# main.net
KiCad netlist of a schematic drawn in EAGLE
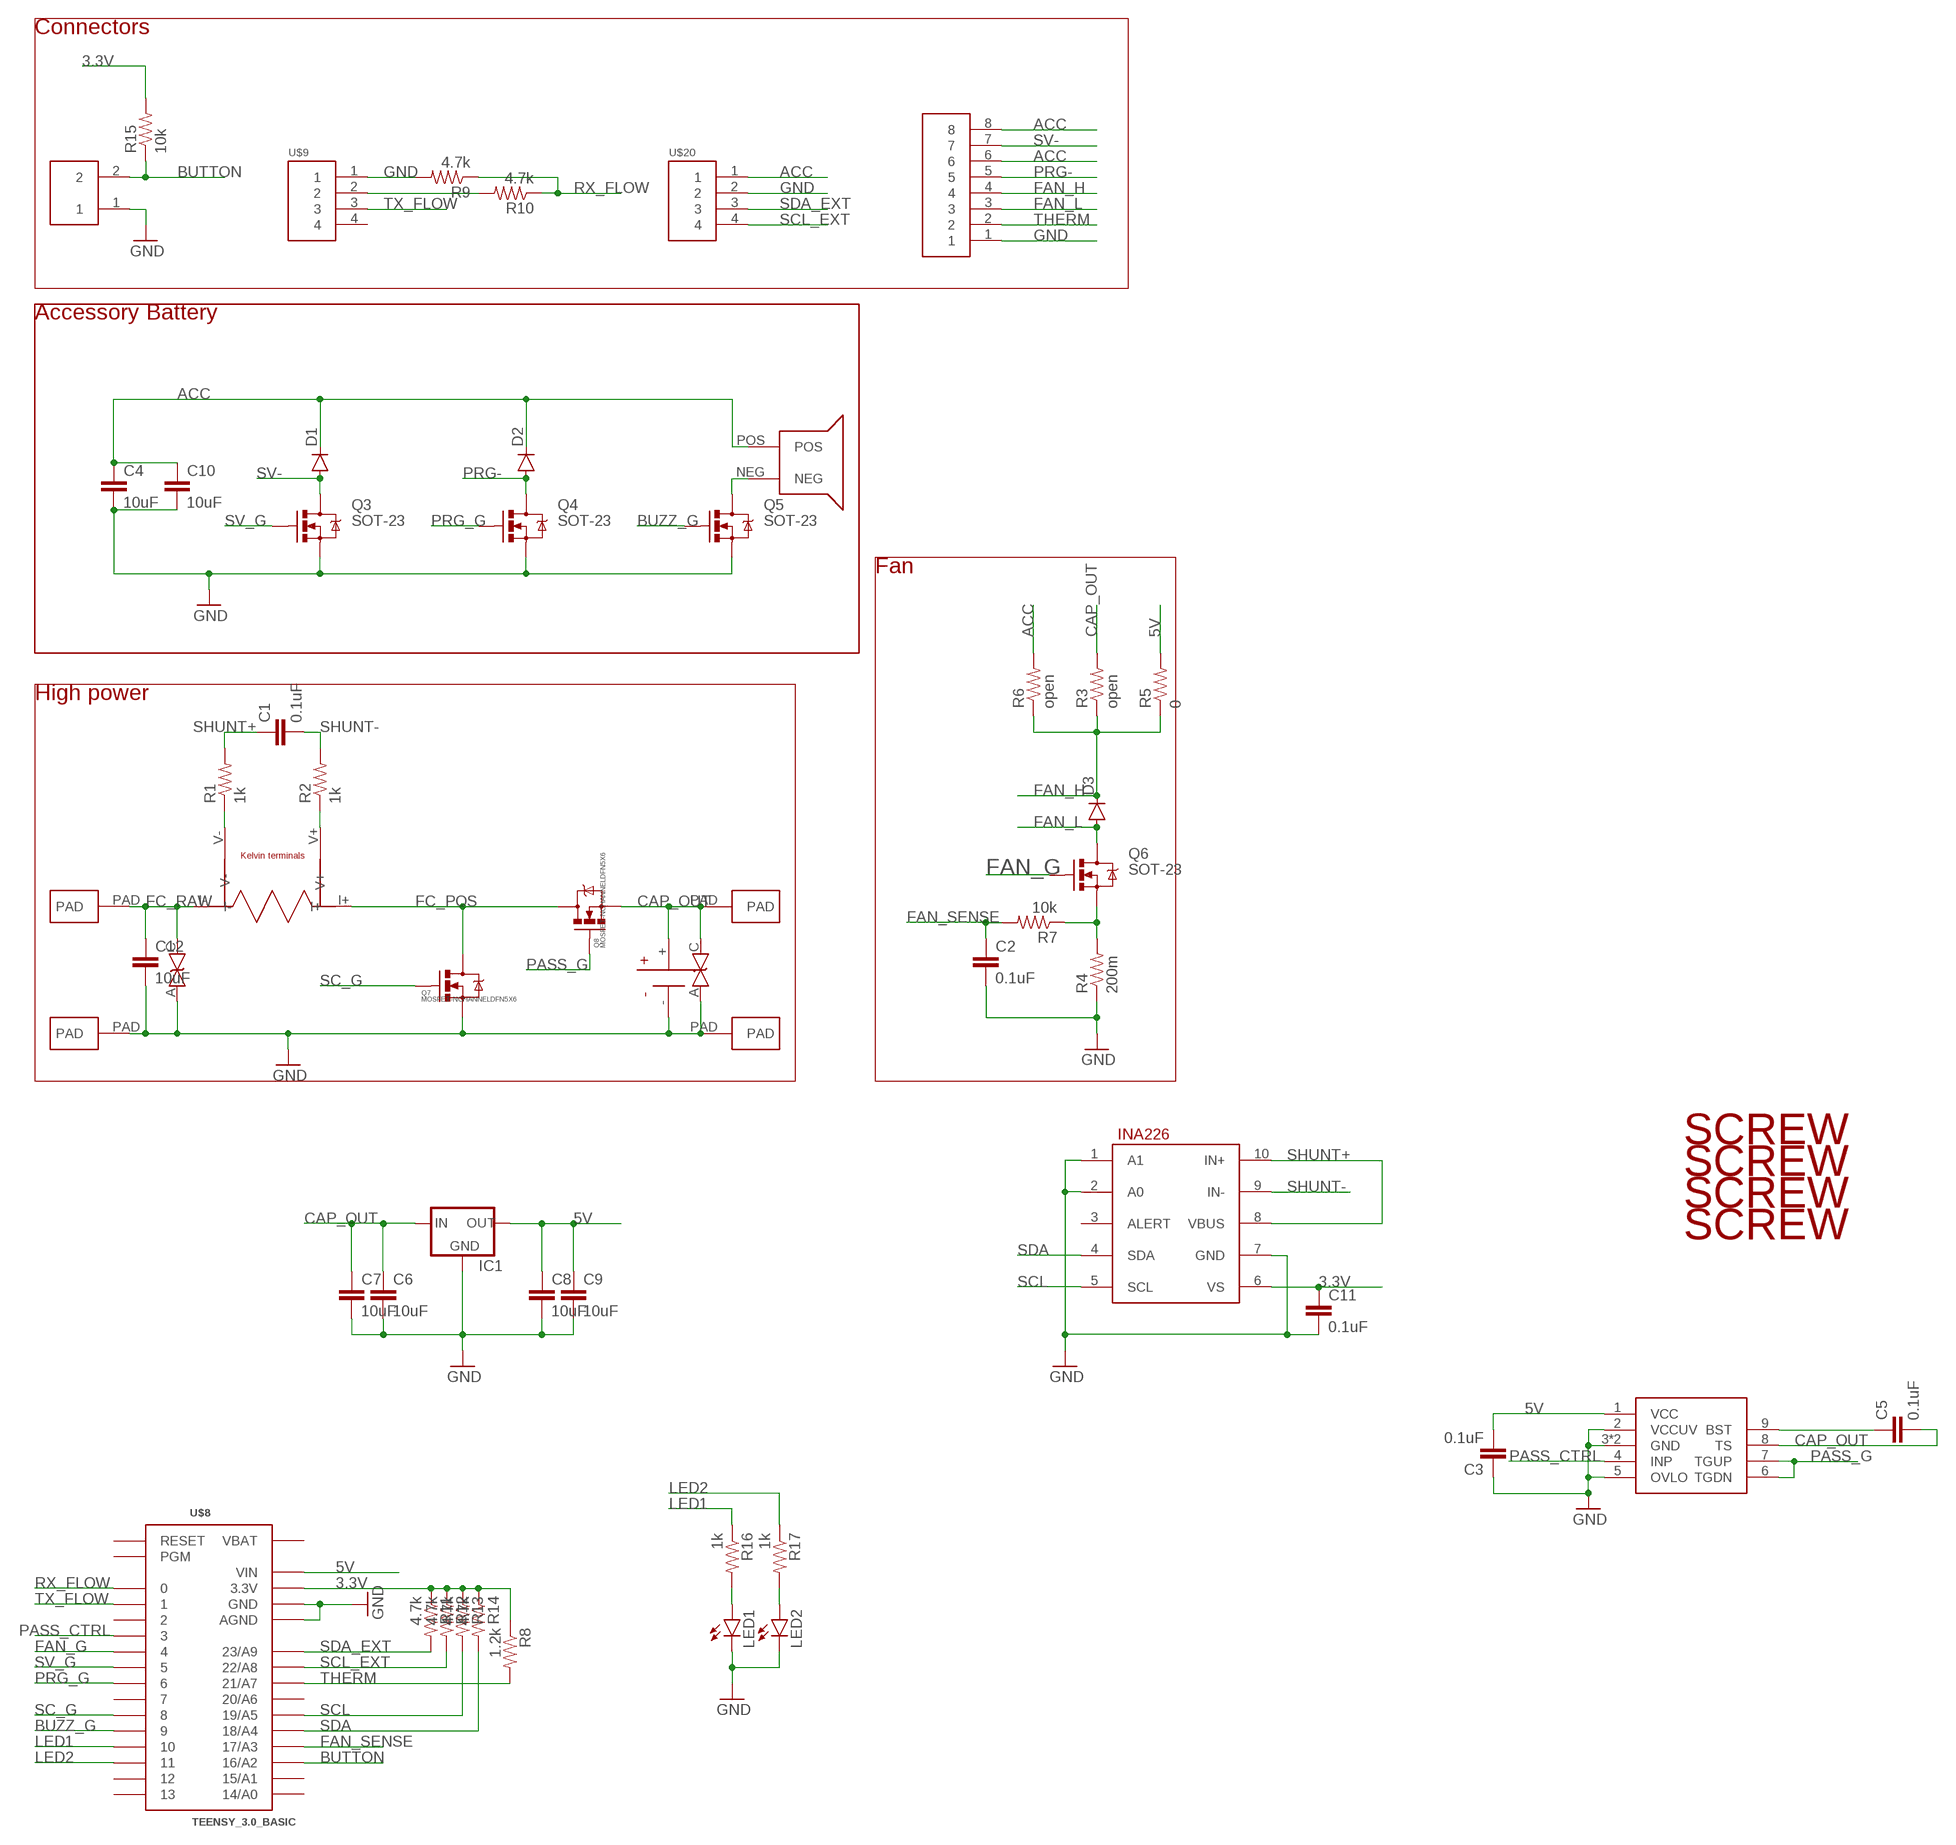
[diagram p0: schematic, sheet 1]

(export (version "E")
  (design (tool "Eeschema 10.0.6"))
  (components
    (comp (ref "C1")
      (value "0.1uF")
      (footprint "eagle-import:0603-CAP")
      (libsource (lib "eagle-import") (part "CAP0603-CAP"))
    )
    (comp (ref "C2")
      (value "0.1uF")
      (footprint "eagle-import:0603-CAP")
      (libsource (lib "eagle-import") (part "CAP0603-CAP"))
    )
    (comp (ref "C3")
      (value "0.1uF")
      (footprint "eagle-import:0603-CAP")
      (libsource (lib "eagle-import") (part "CAP0603-CAP"))
    )
    (comp (ref "C4")
      (value "10uF")
      (footprint "eagle-import:1206")
      (libsource (lib "eagle-import") (part "CAP1206"))
    )
    (comp (ref "C5")
      (value "0.1uF")
      (footprint "eagle-import:0603-CAP")
      (libsource (lib "eagle-import") (part "CAP0603-CAP"))
    )
    (comp (ref "C6")
      (value "10uF")
      (footprint "eagle-import:1206")
      (libsource (lib "eagle-import") (part "CAP1206"))
    )
    (comp (ref "C7")
      (value "10uF")
      (footprint "eagle-import:1206")
      (libsource (lib "eagle-import") (part "CAP1206"))
    )
    (comp (ref "C8")
      (value "10uF")
      (footprint "eagle-import:1206")
      (libsource (lib "eagle-import") (part "CAP1206"))
    )
    (comp (ref "C9")
      (value "10uF")
      (footprint "eagle-import:1206")
      (libsource (lib "eagle-import") (part "CAP1206"))
    )
    (comp (ref "C10")
      (value "10uF")
      (footprint "eagle-import:1206")
      (libsource (lib "eagle-import") (part "CAP1206"))
    )
    (comp (ref "C11")
      (value "0.1uF")
      (footprint "eagle-import:0603-CAP")
      (libsource (lib "eagle-import") (part "CAP0603-CAP"))
    )
    (comp (ref "C12")
      (value "10uF")
      (footprint "eagle-import:1206")
      (libsource (lib "eagle-import") (part "CAP1206"))
    )
    (comp (ref "D1")
      (value "DIODESOD123")
      (footprint "eagle-import:SOD-123")
      (libsource (lib "eagle-import") (part "DIODESOD123"))
    )
    (comp (ref "D2")
      (value "DIODESOD123")
      (footprint "eagle-import:SOD-123")
      (libsource (lib "eagle-import") (part "DIODESOD123"))
    )
    (comp (ref "D3")
      (value "DIODESOD123")
      (footprint "eagle-import:SOD-123")
      (libsource (lib "eagle-import") (part "DIODESOD123"))
    )
    (comp (ref "IC1")
      (value "V_REG_78XXV78W")
      (footprint "eagle-import:V78W")
      (libsource (lib "eagle-import") (part "V_REG_78XXV78W"))
    )
    (comp (ref "LED1")
      (value "LED1206")
      (footprint "eagle-import:LED-1206")
      (libsource (lib "eagle-import") (part "LED1206"))
    )
    (comp (ref "LED2")
      (value "LED1206")
      (footprint "eagle-import:LED-1206")
      (libsource (lib "eagle-import") (part "LED1206"))
    )
    (comp (ref "Q3")
      (value "SOT-23")
      (footprint "eagle-import:SOT23-3")
      (libsource (lib "eagle-import") (part "MOSFET-NCHANNELBSS123LT1G"))
    )
    (comp (ref "Q4")
      (value "SOT-23")
      (footprint "eagle-import:SOT23-3")
      (libsource (lib "eagle-import") (part "MOSFET-NCHANNELBSS123LT1G"))
    )
    (comp (ref "Q5")
      (value "SOT-23")
      (footprint "eagle-import:SOT23-3")
      (libsource (lib "eagle-import") (part "MOSFET-NCHANNELBSS123LT1G"))
    )
    (comp (ref "Q6")
      (value "SOT-23")
      (footprint "eagle-import:SOT23-3")
      (libsource (lib "eagle-import") (part "MOSFET-NCHANNELBSS123LT1G"))
    )
    (comp (ref "Q7")
      (value "MOSFET-NCHANNELDFN5X6")
      (footprint "eagle-import:DFN5X6")
      (libsource (lib "eagle-import") (part "MOSFET-NCHANNELDFN5X6"))
    )
    (comp (ref "Q8")
      (value "MOSFET-NCHANNELDFN5X6")
      (footprint "eagle-import:DFN5X6")
      (libsource (lib "eagle-import") (part "MOSFET-NCHANNELDFN5X6"))
    )
    (comp (ref "R1")
      (value "1k")
      (footprint "eagle-import:0603-RES")
      (libsource (lib "eagle-import") (part "RESISTOR0603-RES"))
    )
    (comp (ref "R2")
      (value "1k")
      (footprint "eagle-import:0603-RES")
      (libsource (lib "eagle-import") (part "RESISTOR0603-RES"))
    )
    (comp (ref "R3")
      (value "open")
      (footprint "eagle-import:0603-RES")
      (libsource (lib "eagle-import") (part "RESISTOR0603-RES"))
    )
    (comp (ref "R4")
      (value "200m")
      (footprint "eagle-import:0603-RES")
      (libsource (lib "eagle-import") (part "RESISTOR0603-RES"))
    )
    (comp (ref "R5")
      (value "0")
      (footprint "eagle-import:0603-RES")
      (libsource (lib "eagle-import") (part "RESISTOR0603-RES"))
    )
    (comp (ref "R6")
      (value "open")
      (footprint "eagle-import:0603-RES")
      (libsource (lib "eagle-import") (part "RESISTOR0603-RES"))
    )
    (comp (ref "R7")
      (value "10k")
      (footprint "eagle-import:0603-RES")
      (libsource (lib "eagle-import") (part "RESISTOR0603-RES"))
    )
    (comp (ref "R8")
      (value "1.2k")
      (footprint "eagle-import:0603-RES")
      (libsource (lib "eagle-import") (part "RESISTOR0603-RES"))
    )
    (comp (ref "R9")
      (value "4.7k")
      (footprint "eagle-import:0603-RES")
      (libsource (lib "eagle-import") (part "RESISTOR0603-RES"))
    )
    (comp (ref "R10")
      (value "4.7k")
      (footprint "eagle-import:0603-RES")
      (libsource (lib "eagle-import") (part "RESISTOR0603-RES"))
    )
    (comp (ref "R11")
      (value "4.7k")
      (footprint "eagle-import:0603-RES")
      (libsource (lib "eagle-import") (part "RESISTOR0603-RES"))
    )
    (comp (ref "R12")
      (value "4.7k")
      (footprint "eagle-import:0603-RES")
      (libsource (lib "eagle-import") (part "RESISTOR0603-RES"))
    )
    (comp (ref "R13")
      (value "4.7k")
      (footprint "eagle-import:0603-RES")
      (libsource (lib "eagle-import") (part "RESISTOR0603-RES"))
    )
    (comp (ref "R14")
      (value "4.7k")
      (footprint "eagle-import:0603-RES")
      (libsource (lib "eagle-import") (part "RESISTOR0603-RES"))
    )
    (comp (ref "R15")
      (value "10k")
      (footprint "eagle-import:0603-RES")
      (libsource (lib "eagle-import") (part "RESISTOR0603-RES"))
    )
    (comp (ref "R16")
      (value "1k")
      (footprint "eagle-import:0603-RES")
      (libsource (lib "eagle-import") (part "RESISTOR0603-RES"))
    )
    (comp (ref "R17")
      (value "1k")
      (footprint "eagle-import:0603-RES")
      (libsource (lib "eagle-import") (part "RESISTOR0603-RES"))
    )
    (comp (ref "U$1")
      (value "SHUNT_KELVIN")
      (footprint "eagle-import:2512_KELVIN")
      (libsource (lib "eagle-import") (part "SHUNT_KELVIN"))
    )
    (comp (ref "U$2")
      (value "INA226")
      (footprint "eagle-import:PSOP-10")
      (libsource (lib "eagle-import") (part "INA226"))
    )
    (comp (ref "U$3")
      (value "PAD")
      (footprint "eagle-import:PAD")
      (libsource (lib "eagle-import") (part "PAD"))
    )
    (comp (ref "U$4")
      (value "PAD")
      (footprint "eagle-import:PAD")
      (libsource (lib "eagle-import") (part "PAD"))
    )
    (comp (ref "U$5")
      (value "HEADER8")
      (footprint "eagle-import:8PINVALULOK")
      (libsource (lib "eagle-import") (part "HEADER8"))
    )
    (comp (ref "U$6")
      (value "LTC7001")
      (footprint "eagle-import:PSOP-10-EP")
      (libsource (lib "eagle-import") (part "LTC7001"))
    )
    (comp (ref "U$7")
      (value "BUZZER12MM")
      (footprint "eagle-import:BUZZER_12MM")
      (libsource (lib "eagle-import") (part "BUZZER12MM"))
    )
    (comp (ref "U$8")
      (value "TEENSY_3.0_BASIC")
      (footprint "eagle-import:TEENSY_3.0_BASIC")
      (libsource (lib "eagle-import") (part "TEENSY_3.0_BASIC"))
    )
    (comp (ref "U$9")
      (value "HEADER4VALULOK")
      (footprint "eagle-import:4PINVALULOK")
      (libsource (lib "eagle-import") (part "HEADER4VALULOK"))
    )
    (comp (ref "U$10")
      (value "PAD")
      (footprint "eagle-import:PAD")
      (libsource (lib "eagle-import") (part "PAD"))
    )
    (comp (ref "U$11")
      (value "PAD")
      (footprint "eagle-import:PAD")
      (libsource (lib "eagle-import") (part "PAD"))
    )
    (comp (ref "U$12")
      (value "CAP-AL_ELECTROLYTIC")
      (footprint "eagle-import:CAP-RADIAL")
      (libsource (lib "eagle-import") (part "CAP-AL_ELECTROLYTIC"))
    )
    (comp (ref "U$13")
      (value "HEADER2")
      (footprint "eagle-import:2PINVALULOK")
      (libsource (lib "eagle-import") (part "HEADER2"))
    )
    (comp (ref "U$14")
      (value "SCREW")
      (footprint "eagle-import:M3HOLE")
      (libsource (lib "eagle-import") (part "SCREW"))
    )
    (comp (ref "U$15")
      (value "SCREW")
      (footprint "eagle-import:M3HOLE")
      (libsource (lib "eagle-import") (part "SCREW"))
    )
    (comp (ref "U$16")
      (value "TVS_BIDO-214AB")
      (footprint "eagle-import:DO-214AB")
      (libsource (lib "eagle-import") (part "TVS_BIDO-214AB"))
    )
    (comp (ref "U$17")
      (value "TVS_BIDO-214AB")
      (footprint "eagle-import:DO-214AB")
      (libsource (lib "eagle-import") (part "TVS_BIDO-214AB"))
    )
    (comp (ref "U$18")
      (value "SCREW")
      (footprint "eagle-import:M3HOLE")
      (libsource (lib "eagle-import") (part "SCREW"))
    )
    (comp (ref "U$19")
      (value "SCREW")
      (footprint "eagle-import:M3HOLE")
      (libsource (lib "eagle-import") (part "SCREW"))
    )
    (comp (ref "U$20")
      (value "HEADER4VALULOK")
      (footprint "eagle-import:4PINVALULOK")
      (libsource (lib "eagle-import") (part "HEADER4VALULOK"))
    )
  )
  (nets
    (net (code "1") (name "/3.3V") (class "Default")
      (node (ref "C11") (pin "1") (pinfunction "1_1") (pintype "passive"))
      (node (ref "R11") (pin "1") (pinfunction "1_1") (pintype "passive"))
      (node (ref "R12") (pin "1") (pinfunction "1_1") (pintype "passive"))
      (node (ref "R13") (pin "1") (pinfunction "1_1") (pintype "passive"))
      (node (ref "R14") (pin "1") (pinfunction "1_1") (pintype "passive"))
      (node (ref "R15") (pin "2") (pinfunction "2_2") (pintype "passive"))
      (node (ref "R8") (pin "1") (pinfunction "1_1") (pintype "passive"))
      (node (ref "U$2") (pin "6") (pinfunction "VS_6") (pintype "bidirectional"))
      (node (ref "U$8") (pin "3.3V") (pinfunction "3.3V_3.3V") (pintype "power_in"))
      (node (ref "U$8") (pin "3.3V1") (pinfunction "3.3V_3.3V1") (pintype "power_in"))
    )
    (net (code "2") (name "/5V") (class "Default")
      (node (ref "C3") (pin "2") (pinfunction "2_2") (pintype "passive"))
      (node (ref "C8") (pin "1") (pinfunction "1_1") (pintype "passive"))
      (node (ref "C9") (pin "1") (pinfunction "1_1") (pintype "passive"))
      (node (ref "IC1") (pin "OUT") (pinfunction "OUT_OUT") (pintype "output"))
      (node (ref "R5") (pin "2") (pinfunction "2_2") (pintype "passive"))
      (node (ref "U$6") (pin "1") (pinfunction "VCC_1") (pintype "bidirectional"))
      (node (ref "U$8") (pin "VIN") (pinfunction "VIN_VIN") (pintype "power_in"))
    )
    (net (code "3") (name "/ACC") (class "Default")
      (node (ref "C10") (pin "1") (pinfunction "1_1") (pintype "passive"))
      (node (ref "C4") (pin "1") (pinfunction "1_1") (pintype "passive"))
      (node (ref "D1") (pin "C") (pinfunction "C_C") (pintype "passive"))
      (node (ref "D2") (pin "C") (pinfunction "C_C") (pintype "passive"))
      (node (ref "R6") (pin "2") (pinfunction "2_2") (pintype "passive"))
      (node (ref "U$20") (pin "1") (pinfunction "1_1") (pintype "bidirectional"))
      (node (ref "U$5") (pin "6") (pinfunction "6_6") (pintype "bidirectional"))
      (node (ref "U$5") (pin "8") (pinfunction "8_8") (pintype "bidirectional"))
      (node (ref "U$7") (pin "POS") (pinfunction "POS_POS") (pintype "bidirectional"))
    )
    (net (code "4") (name "/BUTTON") (class "Default")
      (node (ref "R15") (pin "1") (pinfunction "1_1") (pintype "passive"))
      (node (ref "U$13") (pin "2") (pinfunction "2_2") (pintype "bidirectional"))
      (node (ref "U$8") (pin "16/A2") (pinfunction "16/A2_16/A2") (pintype "bidirectional"))
    )
    (net (code "5") (name "/BUZZ_G") (class "Default")
      (node (ref "Q5") (pin "1") (pinfunction "G_1") (pintype "passive"))
      (node (ref "U$8") (pin "9") (pinfunction "9_9") (pintype "bidirectional"))
    )
    (net (code "6") (name "/CAP_OUT") (class "Default")
      (node (ref "C5") (pin "2") (pinfunction "2_2") (pintype "passive"))
      (node (ref "C6") (pin "1") (pinfunction "1_1") (pintype "passive"))
      (node (ref "C7") (pin "1") (pinfunction "1_1") (pintype "passive"))
      (node (ref "IC1") (pin "IN") (pinfunction "IN_IN") (pintype "input"))
      (node (ref "Q8") (pin "1") (pinfunction "S_1") (pintype "passive"))
      (node (ref "Q8") (pin "2") (pinfunction "S_2") (pintype "passive"))
      (node (ref "Q8") (pin "3") (pinfunction "S_3") (pintype "passive"))
      (node (ref "R3") (pin "2") (pinfunction "2_2") (pintype "passive"))
      (node (ref "U$10") (pin "PAD") (pinfunction "PAD_PAD") (pintype "bidirectional"))
      (node (ref "U$12") (pin "+") (pinfunction "V+_+") (pintype "bidirectional"))
      (node (ref "U$17") (pin "C") (pinfunction "2_C") (pintype "bidirectional"))
      (node (ref "U$6") (pin "8") (pinfunction "TS_8") (pintype "bidirectional"))
    )
    (net (code "7") (name "/FAN_G") (class "Default")
      (node (ref "Q6") (pin "1") (pinfunction "G_1") (pintype "passive"))
      (node (ref "U$8") (pin "4") (pinfunction "4_4") (pintype "bidirectional"))
    )
    (net (code "8") (name "/FAN_H") (class "Default")
      (node (ref "D3") (pin "C") (pinfunction "C_C") (pintype "passive"))
      (node (ref "R3") (pin "1") (pinfunction "1_1") (pintype "passive"))
      (node (ref "R5") (pin "1") (pinfunction "1_1") (pintype "passive"))
      (node (ref "R6") (pin "1") (pinfunction "1_1") (pintype "passive"))
      (node (ref "U$5") (pin "4") (pinfunction "4_4") (pintype "bidirectional"))
    )
    (net (code "9") (name "/FAN_L") (class "Default")
      (node (ref "D3") (pin "A") (pinfunction "A_A") (pintype "passive"))
      (node (ref "Q6") (pin "3") (pinfunction "D_3") (pintype "passive"))
      (node (ref "U$5") (pin "3") (pinfunction "3_3") (pintype "bidirectional"))
    )
    (net (code "10") (name "/FAN_SENSE") (class "Default")
      (node (ref "C2") (pin "1") (pinfunction "1_1") (pintype "passive"))
      (node (ref "R7") (pin "2") (pinfunction "2_2") (pintype "passive"))
      (node (ref "U$8") (pin "17/A3") (pinfunction "17/A3_17/A3") (pintype "bidirectional"))
    )
    (net (code "11") (name "/FC_POS") (class "Default")
      (node (ref "Q7") (pin "PAD") (pinfunction "D_PAD") (pintype "passive"))
      (node (ref "Q8") (pin "PAD") (pinfunction "D_PAD") (pintype "passive"))
      (node (ref "U$1") (pin "I+") (pinfunction "I+_I+") (pintype "bidirectional"))
    )
    (net (code "12") (name "/FC_RAW") (class "Default")
      (node (ref "C12") (pin "1") (pinfunction "1_1") (pintype "passive"))
      (node (ref "U$1") (pin "I-") (pinfunction "I-_I-") (pintype "bidirectional"))
      (node (ref "U$16") (pin "C") (pinfunction "2_C") (pintype "bidirectional"))
      (node (ref "U$3") (pin "PAD") (pinfunction "PAD_PAD") (pintype "bidirectional"))
    )
    (net (code "13") (name "/LED1") (class "Default")
      (node (ref "R16") (pin "1") (pinfunction "1_1") (pintype "passive"))
      (node (ref "U$8") (pin "10") (pinfunction "10_10") (pintype "bidirectional"))
    )
    (net (code "14") (name "/LED2") (class "Default")
      (node (ref "R17") (pin "1") (pinfunction "1_1") (pintype "passive"))
      (node (ref "U$8") (pin "11") (pinfunction "11_11") (pintype "bidirectional"))
    )
    (net (code "15") (name "/PASS_CTRL") (class "Default")
      (node (ref "U$6") (pin "4") (pinfunction "INP_4") (pintype "bidirectional"))
      (node (ref "U$8") (pin "3") (pinfunction "3_3") (pintype "bidirectional"))
    )
    (net (code "16") (name "/PASS_G") (class "Default")
      (node (ref "Q8") (pin "4") (pinfunction "G_4") (pintype "passive"))
      (node (ref "U$6") (pin "6") (pinfunction "TGDN_6") (pintype "bidirectional"))
      (node (ref "U$6") (pin "7") (pinfunction "TGUP_7") (pintype "bidirectional"))
    )
    (net (code "17") (name "/PRG-") (class "Default")
      (node (ref "D2") (pin "A") (pinfunction "A_A") (pintype "passive"))
      (node (ref "Q4") (pin "3") (pinfunction "D_3") (pintype "passive"))
      (node (ref "U$5") (pin "5") (pinfunction "5_5") (pintype "bidirectional"))
    )
    (net (code "18") (name "/PRG_G") (class "Default")
      (node (ref "Q4") (pin "1") (pinfunction "G_1") (pintype "passive"))
      (node (ref "U$8") (pin "6") (pinfunction "6_6") (pintype "bidirectional"))
    )
    (net (code "19") (name "/RX_FLOW") (class "Default")
      (node (ref "R10") (pin "1") (pinfunction "1_1") (pintype "passive"))
      (node (ref "R9") (pin "1") (pinfunction "1_1") (pintype "passive"))
      (node (ref "U$8") (pin "0") (pinfunction "0_0") (pintype "bidirectional"))
    )
    (net (code "20") (name "/SCL") (class "Default")
      (node (ref "R13") (pin "2") (pinfunction "2_2") (pintype "passive"))
      (node (ref "U$2") (pin "5") (pinfunction "SCL_5") (pintype "bidirectional"))
      (node (ref "U$8") (pin "19/A5") (pinfunction "19/A5_19/A5") (pintype "bidirectional"))
    )
    (net (code "21") (name "/SCL_EXT") (class "Default")
      (node (ref "R12") (pin "2") (pinfunction "2_2") (pintype "passive"))
      (node (ref "U$20") (pin "4") (pinfunction "4_4") (pintype "bidirectional"))
      (node (ref "U$8") (pin "22/A8") (pinfunction "22/A8_22/A8") (pintype "bidirectional"))
    )
    (net (code "22") (name "/SC_G") (class "Default")
      (node (ref "Q7") (pin "4") (pinfunction "G_4") (pintype "passive"))
      (node (ref "U$8") (pin "8") (pinfunction "8_8") (pintype "bidirectional"))
    )
    (net (code "23") (name "/SDA") (class "Default")
      (node (ref "R14") (pin "2") (pinfunction "2_2") (pintype "passive"))
      (node (ref "U$2") (pin "4") (pinfunction "SDA_4") (pintype "bidirectional"))
      (node (ref "U$8") (pin "18/A4") (pinfunction "18/A4_18/A4") (pintype "bidirectional"))
    )
    (net (code "24") (name "/SDA_EXT") (class "Default")
      (node (ref "R11") (pin "2") (pinfunction "2_2") (pintype "passive"))
      (node (ref "U$20") (pin "3") (pinfunction "3_3") (pintype "bidirectional"))
      (node (ref "U$8") (pin "23/A9") (pinfunction "23/A9_23/A9") (pintype "bidirectional"))
    )
    (net (code "25") (name "/SHUNT+") (class "Default")
      (node (ref "C1") (pin "1") (pinfunction "1_1") (pintype "passive"))
      (node (ref "R1") (pin "2") (pinfunction "2_2") (pintype "passive"))
      (node (ref "U$2") (pin "10") (pinfunction "IN+_10") (pintype "bidirectional"))
      (node (ref "U$2") (pin "8") (pinfunction "VBUS_8") (pintype "bidirectional"))
    )
    (net (code "26") (name "/SHUNT-") (class "Default")
      (node (ref "C1") (pin "2") (pinfunction "2_2") (pintype "passive"))
      (node (ref "R2") (pin "2") (pinfunction "2_2") (pintype "passive"))
      (node (ref "U$2") (pin "9") (pinfunction "IN-_9") (pintype "bidirectional"))
    )
    (net (code "27") (name "/SV-") (class "Default")
      (node (ref "D1") (pin "A") (pinfunction "A_A") (pintype "passive"))
      (node (ref "Q3") (pin "3") (pinfunction "D_3") (pintype "passive"))
      (node (ref "U$5") (pin "7") (pinfunction "7_7") (pintype "bidirectional"))
    )
    (net (code "28") (name "/SV_G") (class "Default")
      (node (ref "Q3") (pin "1") (pinfunction "G_1") (pintype "passive"))
      (node (ref "U$8") (pin "5") (pinfunction "5_5") (pintype "bidirectional"))
    )
    (net (code "29") (name "/THERM") (class "Default")
      (node (ref "R8") (pin "2") (pinfunction "2_2") (pintype "passive"))
      (node (ref "U$5") (pin "2") (pinfunction "2_2") (pintype "bidirectional"))
      (node (ref "U$8") (pin "21/A7") (pinfunction "21/A7_21/A7") (pintype "bidirectional"))
    )
    (net (code "30") (name "/TX_FLOW") (class "Default")
      (node (ref "U$8") (pin "1") (pinfunction "1_1") (pintype "bidirectional"))
      (node (ref "U$9") (pin "3") (pinfunction "3_3") (pintype "bidirectional"))
    )
    (net (code "31") (name "/VBAT") (class "Default")
      (node (ref "U$8") (pin "VBAT") (pinfunction "VBAT_VBAT") (pintype "power_in"))
    )
    (net (code "32") (name "GND") (class "Default")
      (node (ref "C10") (pin "2") (pinfunction "2_2") (pintype "passive"))
      (node (ref "C11") (pin "2") (pinfunction "2_2") (pintype "passive"))
      (node (ref "C12") (pin "2") (pinfunction "2_2") (pintype "passive"))
      (node (ref "C2") (pin "2") (pinfunction "2_2") (pintype "passive"))
      (node (ref "C3") (pin "1") (pinfunction "1_1") (pintype "passive"))
      (node (ref "C4") (pin "2") (pinfunction "2_2") (pintype "passive"))
      (node (ref "C6") (pin "2") (pinfunction "2_2") (pintype "passive"))
      (node (ref "C7") (pin "2") (pinfunction "2_2") (pintype "passive"))
      (node (ref "C8") (pin "2") (pinfunction "2_2") (pintype "passive"))
      (node (ref "C9") (pin "2") (pinfunction "2_2") (pintype "passive"))
      (node (ref "IC1") (pin "GND") (pinfunction "GND_GND") (pintype "input"))
      (node (ref "LED1") (pin "C") (pinfunction "C_C") (pintype "passive"))
      (node (ref "LED2") (pin "C") (pinfunction "C_C") (pintype "passive"))
      (node (ref "Q3") (pin "2") (pinfunction "S_2") (pintype "passive"))
      (node (ref "Q4") (pin "2") (pinfunction "S_2") (pintype "passive"))
      (node (ref "Q5") (pin "2") (pinfunction "S_2") (pintype "passive"))
      (node (ref "Q7") (pin "1") (pinfunction "S_1") (pintype "passive"))
      (node (ref "Q7") (pin "2") (pinfunction "S_2") (pintype "passive"))
      (node (ref "Q7") (pin "3") (pinfunction "S_3") (pintype "passive"))
      (node (ref "R4") (pin "1") (pinfunction "1_1") (pintype "passive"))
      (node (ref "R9") (pin "2") (pinfunction "2_2") (pintype "passive"))
      (node (ref "U$11") (pin "PAD") (pinfunction "PAD_PAD") (pintype "bidirectional"))
      (node (ref "U$12") (pin "-") (pinfunction "V-_-") (pintype "bidirectional"))
      (node (ref "U$13") (pin "1") (pinfunction "1_1") (pintype "bidirectional"))
      (node (ref "U$16") (pin "A") (pinfunction "1_A") (pintype "bidirectional"))
      (node (ref "U$17") (pin "A") (pinfunction "1_A") (pintype "bidirectional"))
      (node (ref "U$2") (pin "1") (pinfunction "A1_1") (pintype "bidirectional"))
      (node (ref "U$2") (pin "2") (pinfunction "A0_2") (pintype "bidirectional"))
      (node (ref "U$2") (pin "7") (pinfunction "GND_7") (pintype "bidirectional"))
      (node (ref "U$20") (pin "2") (pinfunction "2_2") (pintype "bidirectional"))
      (node (ref "U$4") (pin "PAD") (pinfunction "PAD_PAD") (pintype "bidirectional"))
      (node (ref "U$5") (pin "1") (pinfunction "1_1") (pintype "bidirectional"))
      (node (ref "U$6") (pin "2") (pinfunction "VCCUV_2") (pintype "bidirectional"))
      (node (ref "U$6") (pin "3") (pinfunction "GND_3") (pintype "bidirectional"))
      (node (ref "U$6") (pin "5") (pinfunction "OVLO_5") (pintype "bidirectional"))
      (node (ref "U$6") (pin "PAD") (pinfunction "GND_PAD") (pintype "bidirectional"))
      (node (ref "U$8") (pin "AGND") (pinfunction "AGND_AGND") (pintype "power_in"))
      (node (ref "U$8") (pin "GND") (pinfunction "GND_GND") (pintype "power_in"))
      (node (ref "U$8") (pin "GND1") (pinfunction "GND_GND1") (pintype "power_in"))
      (node (ref "U$9") (pin "1") (pinfunction "1_1") (pintype "bidirectional"))
    )
    (net (code "33") (name "Net-(LED1-PadA)") (class "Default")
      (node (ref "LED1") (pin "A") (pinfunction "A_A") (pintype "passive"))
      (node (ref "R16") (pin "2") (pinfunction "2_2") (pintype "passive"))
    )
    (net (code "34") (name "Net-(LED2-PadA)") (class "Default")
      (node (ref "LED2") (pin "A") (pinfunction "A_A") (pintype "passive"))
      (node (ref "R17") (pin "2") (pinfunction "2_2") (pintype "passive"))
    )
    (net (code "35") (name "Net-(Q5-D)") (class "Default")
      (node (ref "Q5") (pin "3") (pinfunction "D_3") (pintype "passive"))
      (node (ref "U$7") (pin "NEG") (pinfunction "NEG_NEG") (pintype "bidirectional"))
    )
    (net (code "36") (name "Net-(Q6-S)") (class "Default")
      (node (ref "Q6") (pin "2") (pinfunction "S_2") (pintype "passive"))
      (node (ref "R4") (pin "2") (pinfunction "2_2") (pintype "passive"))
      (node (ref "R7") (pin "1") (pinfunction "1_1") (pintype "passive"))
    )
    (net (code "37") (name "Net-(R1-Pad1)") (class "Default")
      (node (ref "R1") (pin "1") (pinfunction "1_1") (pintype "passive"))
      (node (ref "U$1") (pin "V-") (pinfunction "V-_V-") (pintype "bidirectional"))
    )
    (net (code "38") (name "Net-(R2-Pad1)") (class "Default")
      (node (ref "R2") (pin "1") (pinfunction "1_1") (pintype "passive"))
      (node (ref "U$1") (pin "V+") (pinfunction "V+_V+") (pintype "bidirectional"))
    )
    (net (code "39") (name "Net-(R10-Pad2)") (class "Default")
      (node (ref "R10") (pin "2") (pinfunction "2_2") (pintype "passive"))
      (node (ref "U$9") (pin "2") (pinfunction "2_2") (pintype "bidirectional"))
    )
    (net (code "40") (name "Net-(U$6-BST)") (class "Default")
      (node (ref "C5") (pin "1") (pinfunction "1_1") (pintype "passive"))
      (node (ref "U$6") (pin "9") (pinfunction "BST_9") (pintype "bidirectional"))
    )
    (net (code "41") (name "unconnected-(U$2-ALERT-Pad3)") (class "Default")
      (node (ref "U$2") (pin "3") (pinfunction "ALERT_3") (pintype "bidirectional"))
    )
    (net (code "42") (name "unconnected-(U$8-Pad2)") (class "Default")
      (node (ref "U$8") (pin "2") (pinfunction "2_2") (pintype "bidirectional"))
    )
    (net (code "43") (name "unconnected-(U$8-Pad7)") (class "Default")
      (node (ref "U$8") (pin "7") (pinfunction "7_7") (pintype "bidirectional"))
    )
    (net (code "44") (name "unconnected-(U$8-Pad12)") (class "Default")
      (node (ref "U$8") (pin "12") (pinfunction "12_12") (pintype "bidirectional"))
    )
    (net (code "45") (name "unconnected-(U$8-Pad13)") (class "Default")
      (node (ref "U$8") (pin "13") (pinfunction "13_13") (pintype "bidirectional"))
    )
    (net (code "46") (name "unconnected-(U$8-Pad14{slash}A0)") (class "Default")
      (node (ref "U$8") (pin "14/A0") (pinfunction "14/A0_14/A0") (pintype "bidirectional"))
    )
    (net (code "47") (name "unconnected-(U$8-Pad15{slash}A1)") (class "Default")
      (node (ref "U$8") (pin "15/A1") (pinfunction "15/A1_15/A1") (pintype "bidirectional"))
    )
    (net (code "48") (name "unconnected-(U$8-Pad20{slash}A6)") (class "Default")
      (node (ref "U$8") (pin "20/A6") (pinfunction "20/A6_20/A6") (pintype "bidirectional"))
    )
    (net (code "49") (name "unconnected-(U$8-PadPGM)") (class "Default")
      (node (ref "U$8") (pin "PGM") (pinfunction "PGM_PGM") (pintype "bidirectional"))
    )
    (net (code "50") (name "unconnected-(U$8-PadRESET)") (class "Default")
      (node (ref "U$8") (pin "RESET") (pinfunction "RESET_RESET") (pintype "bidirectional"))
    )
    (net (code "51") (name "unconnected-(U$9-Pad4)") (class "Default")
      (node (ref "U$9") (pin "4") (pinfunction "4_4") (pintype "bidirectional"))
    )
  )
)
